# 1-Schematic_WELCOME_HOME_PCB_BOARD.net
KiCad netlist of a schematic drawn in EasyEDA
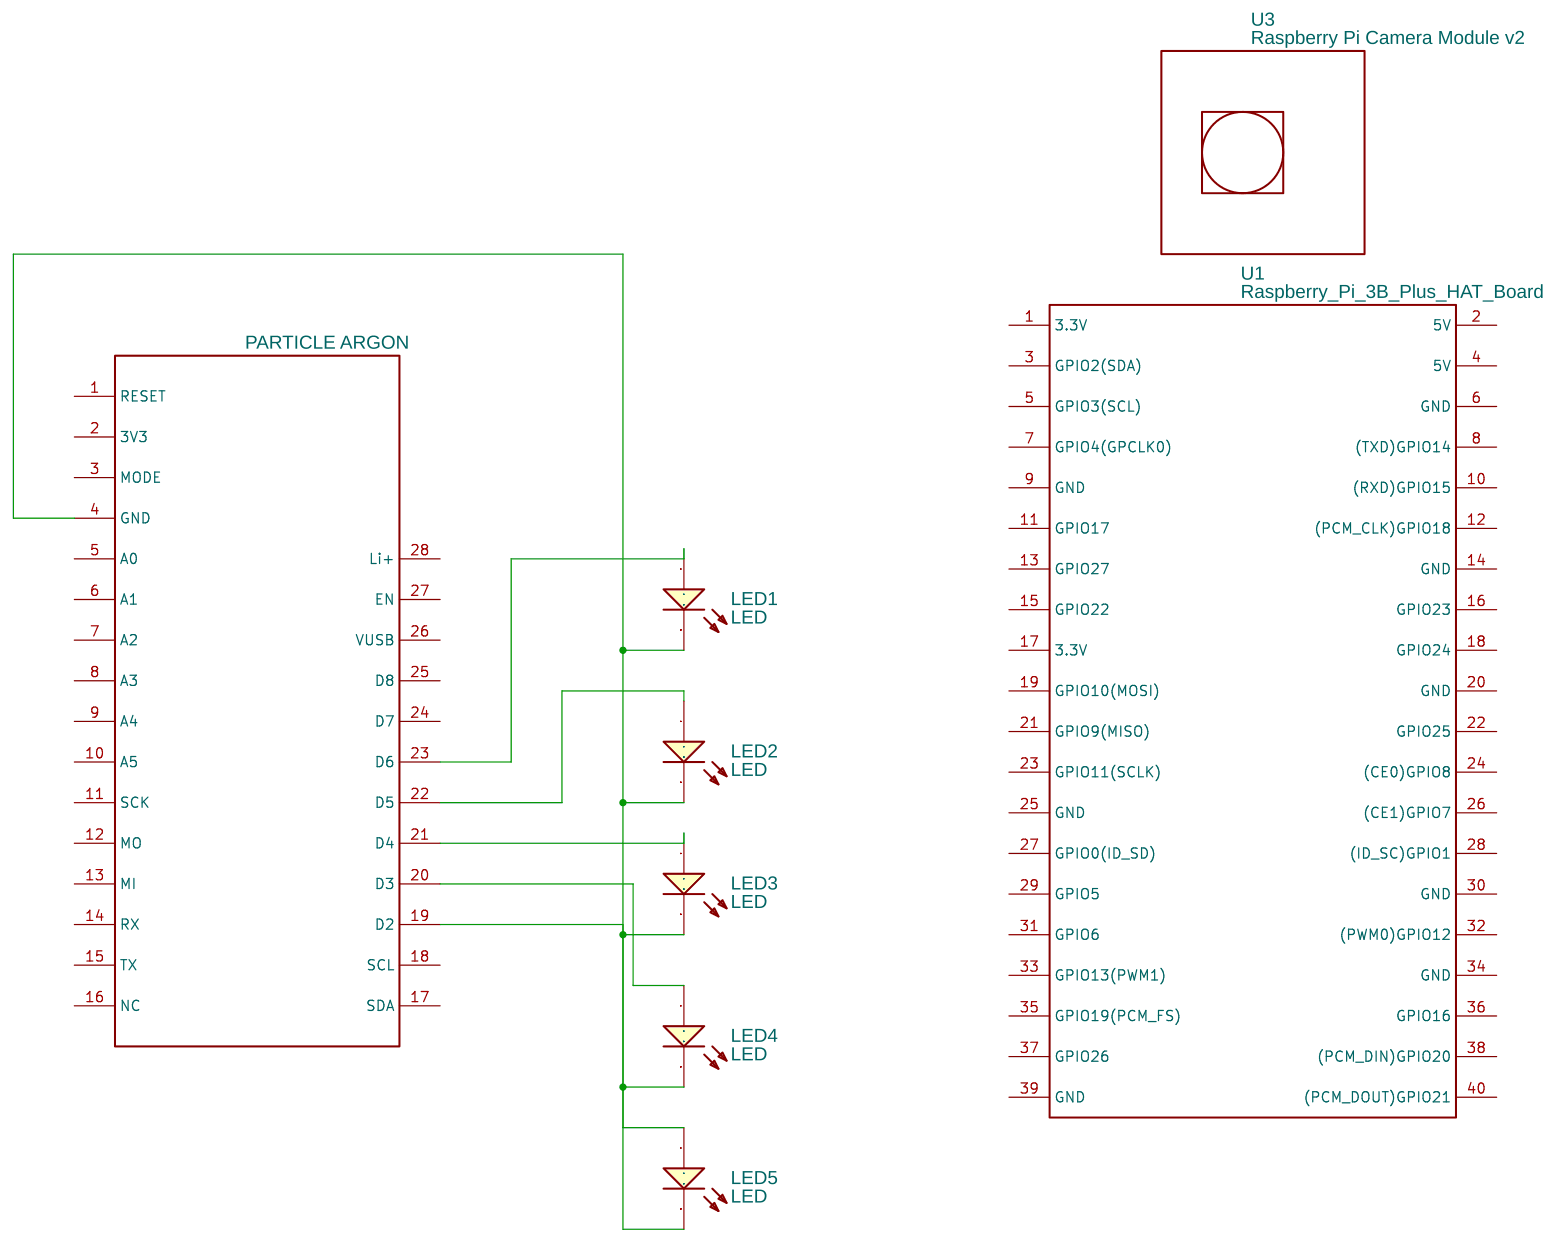
[diagram p0: schematic sheet]

(export (version "E")
  (design (tool "Eeschema 10.0.6"))
  (components
    (comp (ref "LED1")
      (value "LED")
      (fields
        (field (name "BOM_Manufacturer Part") "LEDBlue light")
        (field (name "BOM_Supplier Part") "C69273")
      )
      (libsource (lib "") (part "LED"))
    )
    (comp (ref "LED2")
      (value "LED")
      (fields
        (field (name "BOM_Manufacturer Part") "LEDBlue light")
        (field (name "BOM_Supplier Part") "C69273")
      )
      (libsource (lib "") (part "LED"))
    )
    (comp (ref "LED3")
      (value "LED")
      (fields
        (field (name "BOM_Manufacturer Part") "LEDBlue light")
        (field (name "BOM_Supplier Part") "C69273")
      )
      (libsource (lib "") (part "LED"))
    )
    (comp (ref "LED4")
      (value "LED")
      (fields
        (field (name "BOM_Manufacturer Part") "LEDBlue light")
        (field (name "BOM_Supplier Part") "C69273")
      )
      (libsource (lib "") (part "LED"))
    )
    (comp (ref "LED5")
      (value "LED")
      (fields
        (field (name "BOM_Manufacturer Part") "LEDBlue light")
        (field (name "BOM_Supplier Part") "C69273")
      )
      (libsource (lib "") (part "LED"))
    )
    (comp (ref "U1")
      (value "Raspberry_Pi_3B_Plus_HAT_Board")
      (fields (field (name "BOM_Manufacturer Part") "Raspberry-Pi-3B-Plus-HAT-Board"))
      (libsource (lib "") (part "Raspberry_Pi_3B_Plus_HAT_Board"))
    )
    (comp (ref "U2") (value "PARTICLE ARGON") (libsource (lib "") (part "PARTICLE ARGON")))
    (comp (ref "U3")
      (value "Raspberry Pi Camera Module v2")
      (libsource (lib "") (part "Raspberry Pi Camera Module v2"))
    )
  )
  (nets
    (net (code "1") (name "Net-(U2-D2)") (class "Default")
      (node (ref "LED1") (pin "2") (pinfunction "2_2") (pintype "input"))
      (node (ref "LED2") (pin "2") (pinfunction "2_2") (pintype "input"))
      (node (ref "LED3") (pin "2") (pinfunction "2_2") (pintype "input"))
      (node (ref "LED4") (pin "2") (pinfunction "2_2") (pintype "input"))
      (node (ref "LED5") (pin "1") (pinfunction "1_1") (pintype "input"))
      (node (ref "LED5") (pin "2") (pinfunction "2_2") (pintype "input"))
      (node (ref "U2") (pin "19") (pinfunction "D2_19") (pintype "unspecified"))
      (node (ref "U2") (pin "4") (pinfunction "GND_4") (pintype "unspecified"))
    )
    (net (code "2") (name "Net-(U2-D3)") (class "Default")
      (node (ref "LED4") (pin "1") (pinfunction "1_1") (pintype "input"))
      (node (ref "U2") (pin "20") (pinfunction "D3_20") (pintype "unspecified"))
    )
    (net (code "3") (name "Net-(U2-D4)") (class "Default")
      (node (ref "LED3") (pin "1") (pinfunction "1_1") (pintype "input"))
      (node (ref "U2") (pin "21") (pinfunction "D4_21") (pintype "unspecified"))
    )
    (net (code "4") (name "Net-(U2-D5)") (class "Default")
      (node (ref "LED2") (pin "1") (pinfunction "1_1") (pintype "input"))
      (node (ref "U2") (pin "22") (pinfunction "D5_22") (pintype "unspecified"))
    )
    (net (code "5") (name "Net-(U2-D6)") (class "Default")
      (node (ref "LED1") (pin "1") (pinfunction "1_1") (pintype "input"))
      (node (ref "U2") (pin "23") (pinfunction "D6_23") (pintype "unspecified"))
    )
    (net (code "6") (name "unconnected-(U1-(CE0)GPIO8-Pad24)") (class "Default")
      (node (ref "U1") (pin "24") (pinfunction "(CE0)GPIO8_24") (pintype "unspecified"))
    )
    (net (code "7") (name "unconnected-(U1-(CE1)GPIO7-Pad26)") (class "Default")
      (node (ref "U1") (pin "26") (pinfunction "(CE1)GPIO7_26") (pintype "unspecified"))
    )
    (net (code "8") (name "unconnected-(U1-(ID_SC)GPIO1-Pad28)") (class "Default")
      (node (ref "U1") (pin "28") (pinfunction "(ID_SC)GPIO1_28") (pintype "unspecified"))
    )
    (net (code "9") (name "unconnected-(U1-(PCM_CLK)GPIO18-Pad12)") (class "Default")
      (node (ref "U1") (pin "12") (pinfunction "(PCM_CLK)GPIO18_12") (pintype "unspecified"))
    )
    (net (code "10") (name "unconnected-(U1-(PCM_DIN)GPIO20-Pad38)") (class "Default")
      (node (ref "U1") (pin "38") (pinfunction "(PCM_DIN)GPIO20_38") (pintype "unspecified"))
    )
    (net (code "11") (name "unconnected-(U1-(PCM_DOUT)GPIO21-Pad40)") (class "Default")
      (node (ref "U1") (pin "40") (pinfunction "(PCM_DOUT)GPIO21_40") (pintype "unspecified"))
    )
    (net (code "12") (name "unconnected-(U1-(PWM0)GPIO12-Pad32)") (class "Default")
      (node (ref "U1") (pin "32") (pinfunction "(PWM0)GPIO12_32") (pintype "unspecified"))
    )
    (net (code "13") (name "unconnected-(U1-(RXD)GPIO15-Pad10)") (class "Default")
      (node (ref "U1") (pin "10") (pinfunction "(RXD)GPIO15_10") (pintype "unspecified"))
    )
    (net (code "14") (name "unconnected-(U1-(TXD)GPIO14-Pad8)") (class "Default")
      (node (ref "U1") (pin "8") (pinfunction "(TXD)GPIO14_8") (pintype "unspecified"))
    )
    (net (code "15") (name "unconnected-(U1-3.3V-Pad1)") (class "Default")
      (node (ref "U1") (pin "1") (pinfunction "3.3V_1") (pintype "unspecified"))
    )
    (net (code "16") (name "unconnected-(U1-3.3V-Pad17)") (class "Default")
      (node (ref "U1") (pin "17") (pinfunction "3.3V_17") (pintype "unspecified"))
    )
    (net (code "17") (name "unconnected-(U1-5V-Pad2)") (class "Default")
      (node (ref "U1") (pin "2") (pinfunction "5V_2") (pintype "unspecified"))
    )
    (net (code "18") (name "unconnected-(U1-5V-Pad4)") (class "Default")
      (node (ref "U1") (pin "4") (pinfunction "5V_4") (pintype "unspecified"))
    )
    (net (code "19") (name "unconnected-(U1-GND-Pad6)") (class "Default")
      (node (ref "U1") (pin "6") (pinfunction "GND_6") (pintype "unspecified"))
    )
    (net (code "20") (name "unconnected-(U1-GND-Pad9)") (class "Default")
      (node (ref "U1") (pin "9") (pinfunction "GND_9") (pintype "unspecified"))
    )
    (net (code "21") (name "unconnected-(U1-GND-Pad14)") (class "Default")
      (node (ref "U1") (pin "14") (pinfunction "GND_14") (pintype "unspecified"))
    )
    (net (code "22") (name "unconnected-(U1-GND-Pad20)") (class "Default")
      (node (ref "U1") (pin "20") (pinfunction "GND_20") (pintype "unspecified"))
    )
    (net (code "23") (name "unconnected-(U1-GND-Pad25)") (class "Default")
      (node (ref "U1") (pin "25") (pinfunction "GND_25") (pintype "unspecified"))
    )
    (net (code "24") (name "unconnected-(U1-GND-Pad30)") (class "Default")
      (node (ref "U1") (pin "30") (pinfunction "GND_30") (pintype "unspecified"))
    )
    (net (code "25") (name "unconnected-(U1-GND-Pad34)") (class "Default")
      (node (ref "U1") (pin "34") (pinfunction "GND_34") (pintype "unspecified"))
    )
    (net (code "26") (name "unconnected-(U1-GND-Pad39)") (class "Default")
      (node (ref "U1") (pin "39") (pinfunction "GND_39") (pintype "unspecified"))
    )
    (net (code "27") (name "unconnected-(U1-GPIO0(ID_SD)-Pad27)") (class "Default")
      (node (ref "U1") (pin "27") (pinfunction "GPIO0(ID_SD)_27") (pintype "unspecified"))
    )
    (net (code "28") (name "unconnected-(U1-GPIO2(SDA)-Pad3)") (class "Default")
      (node (ref "U1") (pin "3") (pinfunction "GPIO2(SDA)_3") (pintype "unspecified"))
    )
    (net (code "29") (name "unconnected-(U1-GPIO3(SCL)-Pad5)") (class "Default")
      (node (ref "U1") (pin "5") (pinfunction "GPIO3(SCL)_5") (pintype "unspecified"))
    )
    (net (code "30") (name "unconnected-(U1-GPIO4(GPCLK0)-Pad7)") (class "Default")
      (node (ref "U1") (pin "7") (pinfunction "GPIO4(GPCLK0)_7") (pintype "unspecified"))
    )
    (net (code "31") (name "unconnected-(U1-GPIO5-Pad29)") (class "Default")
      (node (ref "U1") (pin "29") (pinfunction "GPIO5_29") (pintype "unspecified"))
    )
    (net (code "32") (name "unconnected-(U1-GPIO6-Pad31)") (class "Default")
      (node (ref "U1") (pin "31") (pinfunction "GPIO6_31") (pintype "unspecified"))
    )
    (net (code "33") (name "unconnected-(U1-GPIO9(MISO)-Pad21)") (class "Default")
      (node (ref "U1") (pin "21") (pinfunction "GPIO9(MISO)_21") (pintype "unspecified"))
    )
    (net (code "34") (name "unconnected-(U1-GPIO10(MOSI)-Pad19)") (class "Default")
      (node (ref "U1") (pin "19") (pinfunction "GPIO10(MOSI)_19") (pintype "unspecified"))
    )
    (net (code "35") (name "unconnected-(U1-GPIO11(SCLK)-Pad23)") (class "Default")
      (node (ref "U1") (pin "23") (pinfunction "GPIO11(SCLK)_23") (pintype "unspecified"))
    )
    (net (code "36") (name "unconnected-(U1-GPIO13(PWM1)-Pad33)") (class "Default")
      (node (ref "U1") (pin "33") (pinfunction "GPIO13(PWM1)_33") (pintype "unspecified"))
    )
    (net (code "37") (name "unconnected-(U1-GPIO16-Pad36)") (class "Default")
      (node (ref "U1") (pin "36") (pinfunction "GPIO16_36") (pintype "unspecified"))
    )
    (net (code "38") (name "unconnected-(U1-GPIO17-Pad11)") (class "Default")
      (node (ref "U1") (pin "11") (pinfunction "GPIO17_11") (pintype "unspecified"))
    )
    (net (code "39") (name "unconnected-(U1-GPIO19(PCM_FS)-Pad35)") (class "Default")
      (node (ref "U1") (pin "35") (pinfunction "GPIO19(PCM_FS)_35") (pintype "unspecified"))
    )
    (net (code "40") (name "unconnected-(U1-GPIO22-Pad15)") (class "Default")
      (node (ref "U1") (pin "15") (pinfunction "GPIO22_15") (pintype "unspecified"))
    )
    (net (code "41") (name "unconnected-(U1-GPIO23-Pad16)") (class "Default")
      (node (ref "U1") (pin "16") (pinfunction "GPIO23_16") (pintype "unspecified"))
    )
    (net (code "42") (name "unconnected-(U1-GPIO24-Pad18)") (class "Default")
      (node (ref "U1") (pin "18") (pinfunction "GPIO24_18") (pintype "unspecified"))
    )
    (net (code "43") (name "unconnected-(U1-GPIO25-Pad22)") (class "Default")
      (node (ref "U1") (pin "22") (pinfunction "GPIO25_22") (pintype "unspecified"))
    )
    (net (code "44") (name "unconnected-(U1-GPIO26-Pad37)") (class "Default")
      (node (ref "U1") (pin "37") (pinfunction "GPIO26_37") (pintype "unspecified"))
    )
    (net (code "45") (name "unconnected-(U1-GPIO27-Pad13)") (class "Default")
      (node (ref "U1") (pin "13") (pinfunction "GPIO27_13") (pintype "unspecified"))
    )
    (net (code "46") (name "unconnected-(U2-3V3-Pad2)") (class "Default")
      (node (ref "U2") (pin "2") (pinfunction "3V3_2") (pintype "unspecified"))
    )
    (net (code "47") (name "unconnected-(U2-A0-Pad5)") (class "Default")
      (node (ref "U2") (pin "5") (pinfunction "A0_5") (pintype "unspecified"))
    )
    (net (code "48") (name "unconnected-(U2-A1-Pad6)") (class "Default")
      (node (ref "U2") (pin "6") (pinfunction "A1_6") (pintype "unspecified"))
    )
    (net (code "49") (name "unconnected-(U2-A2-Pad7)") (class "Default")
      (node (ref "U2") (pin "7") (pinfunction "A2_7") (pintype "unspecified"))
    )
    (net (code "50") (name "unconnected-(U2-A3-Pad8)") (class "Default")
      (node (ref "U2") (pin "8") (pinfunction "A3_8") (pintype "unspecified"))
    )
    (net (code "51") (name "unconnected-(U2-A4-Pad9)") (class "Default")
      (node (ref "U2") (pin "9") (pinfunction "A4_9") (pintype "unspecified"))
    )
    (net (code "52") (name "unconnected-(U2-A5-Pad10)") (class "Default")
      (node (ref "U2") (pin "10") (pinfunction "A5_10") (pintype "unspecified"))
    )
    (net (code "53") (name "unconnected-(U2-D7-Pad24)") (class "Default")
      (node (ref "U2") (pin "24") (pinfunction "D7_24") (pintype "unspecified"))
    )
    (net (code "54") (name "unconnected-(U2-D8-Pad25)") (class "Default")
      (node (ref "U2") (pin "25") (pinfunction "D8_25") (pintype "unspecified"))
    )
    (net (code "55") (name "unconnected-(U2-EN-Pad27)") (class "Default")
      (node (ref "U2") (pin "27") (pinfunction "EN_27") (pintype "unspecified"))
    )
    (net (code "56") (name "unconnected-(U2-Li+-Pad28)") (class "Default")
      (node (ref "U2") (pin "28") (pinfunction "Li+_28") (pintype "unspecified"))
    )
    (net (code "57") (name "unconnected-(U2-MI-Pad13)") (class "Default")
      (node (ref "U2") (pin "13") (pinfunction "MI_13") (pintype "unspecified"))
    )
    (net (code "58") (name "unconnected-(U2-MO-Pad12)") (class "Default")
      (node (ref "U2") (pin "12") (pinfunction "MO_12") (pintype "unspecified"))
    )
    (net (code "59") (name "unconnected-(U2-MODE-Pad3)") (class "Default")
      (node (ref "U2") (pin "3") (pinfunction "MODE_3") (pintype "unspecified"))
    )
    (net (code "60") (name "unconnected-(U2-NC-Pad16)") (class "Default")
      (node (ref "U2") (pin "16") (pinfunction "NC_16") (pintype "unspecified"))
    )
    (net (code "61") (name "unconnected-(U2-RESET-Pad1)") (class "Default")
      (node (ref "U2") (pin "1") (pinfunction "RESET_1") (pintype "unspecified"))
    )
    (net (code "62") (name "unconnected-(U2-RX-Pad14)") (class "Default")
      (node (ref "U2") (pin "14") (pinfunction "RX_14") (pintype "unspecified"))
    )
    (net (code "63") (name "unconnected-(U2-SCK-Pad11)") (class "Default")
      (node (ref "U2") (pin "11") (pinfunction "SCK_11") (pintype "unspecified"))
    )
    (net (code "64") (name "unconnected-(U2-SCL-Pad18)") (class "Default")
      (node (ref "U2") (pin "18") (pinfunction "SCL_18") (pintype "unspecified"))
    )
    (net (code "65") (name "unconnected-(U2-SDA-Pad17)") (class "Default")
      (node (ref "U2") (pin "17") (pinfunction "SDA_17") (pintype "unspecified"))
    )
    (net (code "66") (name "unconnected-(U2-TX-Pad15)") (class "Default")
      (node (ref "U2") (pin "15") (pinfunction "TX_15") (pintype "unspecified"))
    )
    (net (code "67") (name "unconnected-(U2-VUSB-Pad26)") (class "Default")
      (node (ref "U2") (pin "26") (pinfunction "VUSB_26") (pintype "unspecified"))
    )
  )
)
